# Schematic.net
KiCad netlist of a schematic drawn in Altium Designer
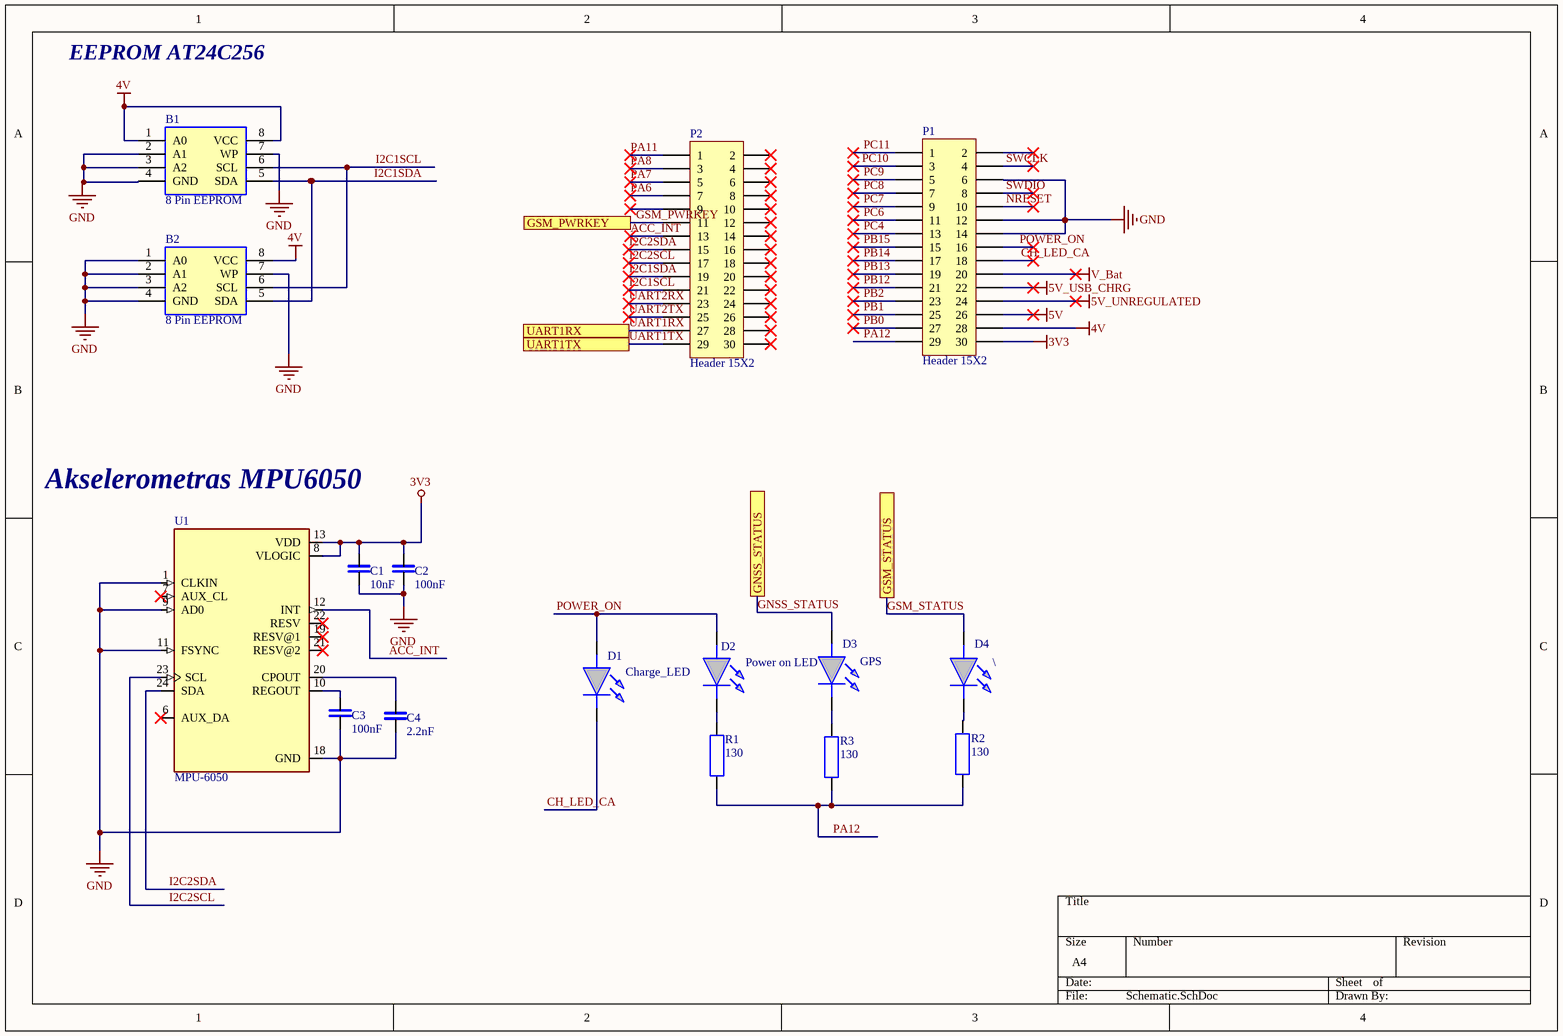
[diagram p0: Schematic.SchDoc]

(export (version "E")
  (design (tool "Eeschema 10.0.6"))
  (components
    (comp (ref "B1")
      (value "8 Pin EEPROM")
      (footprint "AT24C256")
      (fields
        (field (name "MANUFACTURER_PART_NUMBER") "AT24C256C-SSHL-T")
        (field (name "MOUSER PART NUMBER") "556-AT24C256C-SSHL-T")
      )
      (libsource (lib "IC") (part "AT24C256C"))
    )
    (comp (ref "B2")
      (value "8 Pin EEPROM")
      (footprint "AT24C256")
      (fields
        (field (name "MANUFACTURER_PART_NUMBER") "AT24C256C-SSHL-T")
        (field (name "MOUSER PART NUMBER") "556-AT24C256C-SSHL-T")
      )
      (libsource (lib "IC") (part "AT24C256C"))
    )
    (comp (ref "C1")
      (value "10nF")
      (footprint "CAP_0805")
      (fields (field (name "MP") "LD051A270KAB2A"))
      (libsource (lib "Passive_Components") (part "SMT_CAP"))
    )
    (comp (ref "C2")
      (value "100nF")
      (footprint "CAP_0805")
      (fields (field (name "MP") "LD051A270KAB2A"))
      (libsource (lib "Passive_Components") (part "SMT_CAP"))
    )
    (comp (ref "C3")
      (value "100nF")
      (footprint "CAP_0805")
      (fields (field (name "MP") "LD051A270KAB2A"))
      (libsource (lib "Passive_Components") (part "SMT_CAP"))
    )
    (comp (ref "C4")
      (value "2.2nF")
      (footprint "CAP_0805")
      (fields (field (name "MP") "LD051A270KAB2A"))
      (libsource (lib "Passive_Components") (part "SMT_CAP"))
    )
    (comp (ref "D1")
      (value "Charge_LED")
      (footprint "LED_0805")
      (fields
        (field (name "MANUFACTURER_PART_NUMBER") "HSMH-C170")
        (field (name "MOUSER PART NUMBER") "630-HSMH-C170")
      )
      (libsource (lib "Diodes") (part "LED"))
    )
    (comp (ref "D2")
      (value "Power on LED")
      (footprint "LED_0805")
      (fields
        (field (name "MANUFACTURER_PART_NUMBER") "HSMH-C170")
        (field (name "MOUSER PART NUMBER") "630-HSMH-C170")
      )
      (libsource (lib "Diodes") (part "LED"))
    )
    (comp (ref "D3")
      (value "GPS")
      (footprint "LED_0805")
      (fields
        (field (name "MANUFACTURER_PART_NUMBER") "HSMH-C170")
        (field (name "MOUSER PART NUMBER") "630-HSMH-C170")
      )
      (libsource (lib "Diodes") (part "LED"))
    )
    (comp (ref "D4")
      (value "\\")
      (footprint "LED_0805")
      (fields
        (field (name "MANUFACTURER_PART_NUMBER") "HSMH-C170")
        (field (name "MOUSER PART NUMBER") "630-HSMH-C170")
      )
      (libsource (lib "Diodes") (part "LED"))
    )
    (comp (ref "P1")
      (value "Header 15X2")
      (footprint "HDR2X15")
      (description "Header, 15-Pin, Dual row")
      (fields (field (name "PUBLISHER") "Altium Limited"))
      (libsource (lib "Miscellaneous Connectors") (part "Header 15X2"))
    )
    (comp (ref "P2")
      (value "Header 15X2")
      (footprint "HDR2X15")
      (description "Header, 15-Pin, Dual row")
      (fields (field (name "PUBLISHER") "Altium Limited"))
      (libsource (lib "Miscellaneous Connectors") (part "Header 15X2"))
    )
    (comp (ref "R1")
      (value "130")
      (footprint "RES_0805")
      (fields
        (field (name "MP") "2-2176053-0")
        (field (name "TOLERANCE") "1%")
        (field (name "MF") "TE Connectivity")
      )
      (libsource (lib "Passive_Components") (part "SMT_RES"))
    )
    (comp (ref "R2")
      (value "130")
      (footprint "RES_0805")
      (fields
        (field (name "MP") "2-2176053-0")
        (field (name "TOLERANCE") "1%")
        (field (name "MF") "TE Connectivity")
      )
      (libsource (lib "Passive_Components") (part "SMT_RES"))
    )
    (comp (ref "R3")
      (value "130")
      (footprint "RES_0805")
      (fields
        (field (name "MP") "2-2176053-0")
        (field (name "TOLERANCE") "1%")
        (field (name "MF") "TE Connectivity")
      )
      (libsource (lib "Passive_Components") (part "SMT_RES"))
    )
    (comp (ref "U1")
      (value "MPU-6050")
      (footprint "MPU_6050")
      (fields (field (name "MF") "TDK InvenSense"))
      (libsource (lib "IC") (part "MPU-6050"))
    )
  )
  (nets
    (net (code "2") (name "/ACC_INT") (class "Default")
      (node (ref "P2") (pin "13") (pinfunction "13_13") (pintype "passive"))
      (node (ref "U1") (pin "12") (pinfunction "INT_12") (pintype "output"))
    )
    (net (code "3") (name "/CH_LED_CA") (class "Default")
      (node (ref "D1") (pin "1") (pinfunction "K_1") (pintype "passive"))
      (node (ref "P1") (pin "18") (pinfunction "18_18") (pintype "passive"))
    )
    (net (code "4") (name "/GNSS_STATUS") (class "Default")
      (node (ref "D3") (pin "2") (pinfunction "A_2") (pintype "passive"))
    )
    (net (code "5") (name "/GSM_PWRKEY") (class "Default")
      (node (ref "P2") (pin "11") (pinfunction "11_11") (pintype "passive"))
    )
    (net (code "6") (name "/GSM_STATUS") (class "Default")
      (node (ref "D4") (pin "2") (pinfunction "A_2") (pintype "passive"))
    )
    (net (code "7") (name "/I2C1SCL") (class "Default")
      (node (ref "B1") (pin "6") (pinfunction "SCL_6") (pintype "passive"))
      (node (ref "B2") (pin "6") (pinfunction "SCL_6") (pintype "passive"))
      (node (ref "P2") (pin "21") (pinfunction "21_21") (pintype "passive"))
    )
    (net (code "8") (name "/I2C1SDA") (class "Default")
      (node (ref "B1") (pin "5") (pinfunction "SDA_5") (pintype "passive"))
      (node (ref "B2") (pin "5") (pinfunction "SDA_5") (pintype "passive"))
      (node (ref "P2") (pin "19") (pinfunction "19_19") (pintype "passive"))
    )
    (net (code "9") (name "/I2C2SCL") (class "Default")
      (node (ref "P2") (pin "17") (pinfunction "17_17") (pintype "passive"))
      (node (ref "U1") (pin "23") (pinfunction "SCL_23") (pintype "input"))
    )
    (net (code "10") (name "/I2C2SDA") (class "Default")
      (node (ref "P2") (pin "15") (pinfunction "15_15") (pintype "passive"))
      (node (ref "U1") (pin "24") (pinfunction "SDA_24") (pintype "bidirectional"))
    )
    (net (code "11") (name "/NRESET") (class "Default")
      (node (ref "P1") (pin "10") (pinfunction "10_10") (pintype "passive+no_connect"))
    )
    (net (code "12") (name "/PA6") (class "Default")
      (node (ref "P2") (pin "7") (pinfunction "7_7") (pintype "passive+no_connect"))
    )
    (net (code "13") (name "/PA7") (class "Default")
      (node (ref "P2") (pin "5") (pinfunction "5_5") (pintype "passive+no_connect"))
    )
    (net (code "14") (name "/PA8") (class "Default")
      (node (ref "P2") (pin "3") (pinfunction "3_3") (pintype "passive+no_connect"))
    )
    (net (code "15") (name "/PA11") (class "Default")
      (node (ref "P2") (pin "1") (pinfunction "1_1") (pintype "passive+no_connect"))
    )
    (net (code "16") (name "/PA12") (class "Default")
      (node (ref "P1") (pin "29") (pinfunction "29_29") (pintype "passive"))
      (node (ref "R1") (pin "1") (pinfunction "1_1") (pintype "passive"))
      (node (ref "R2") (pin "1") (pinfunction "1_1") (pintype "passive"))
      (node (ref "R3") (pin "1") (pinfunction "1_1") (pintype "passive"))
    )
    (net (code "17") (name "/PB0") (class "Default")
      (node (ref "P1") (pin "27") (pinfunction "27_27") (pintype "passive+no_connect"))
    )
    (net (code "18") (name "/PB1") (class "Default")
      (node (ref "P1") (pin "25") (pinfunction "25_25") (pintype "passive+no_connect"))
    )
    (net (code "19") (name "/PB2") (class "Default")
      (node (ref "P1") (pin "23") (pinfunction "23_23") (pintype "passive+no_connect"))
    )
    (net (code "20") (name "/PB12") (class "Default")
      (node (ref "P1") (pin "21") (pinfunction "21_21") (pintype "passive+no_connect"))
    )
    (net (code "21") (name "/PB13") (class "Default")
      (node (ref "P1") (pin "19") (pinfunction "19_19") (pintype "passive+no_connect"))
    )
    (net (code "22") (name "/PB14") (class "Default")
      (node (ref "P1") (pin "17") (pinfunction "17_17") (pintype "passive+no_connect"))
    )
    (net (code "23") (name "/PB15") (class "Default")
      (node (ref "P1") (pin "15") (pinfunction "15_15") (pintype "passive+no_connect"))
    )
    (net (code "24") (name "/PC4") (class "Default")
      (node (ref "P1") (pin "13") (pinfunction "13_13") (pintype "passive+no_connect"))
    )
    (net (code "25") (name "/PC6") (class "Default")
      (node (ref "P1") (pin "11") (pinfunction "11_11") (pintype "passive+no_connect"))
    )
    (net (code "26") (name "/PC7") (class "Default")
      (node (ref "P1") (pin "9") (pinfunction "9_9") (pintype "passive+no_connect"))
    )
    (net (code "27") (name "/PC8") (class "Default")
      (node (ref "P1") (pin "7") (pinfunction "7_7") (pintype "passive+no_connect"))
    )
    (net (code "28") (name "/PC9") (class "Default")
      (node (ref "P1") (pin "5") (pinfunction "5_5") (pintype "passive+no_connect"))
    )
    (net (code "29") (name "/PC10") (class "Default")
      (node (ref "P1") (pin "3") (pinfunction "3_3") (pintype "passive+no_connect"))
    )
    (net (code "30") (name "/PC11") (class "Default")
      (node (ref "P1") (pin "1") (pinfunction "1_1") (pintype "passive+no_connect"))
    )
    (net (code "31") (name "/POWER_ON") (class "Default")
      (node (ref "D1") (pin "2") (pinfunction "A_2") (pintype "passive"))
      (node (ref "D2") (pin "2") (pinfunction "A_2") (pintype "passive"))
      (node (ref "P1") (pin "16") (pinfunction "16_16") (pintype "passive"))
    )
    (net (code "32") (name "/SWCLK") (class "Default")
      (node (ref "P1") (pin "4") (pinfunction "4_4") (pintype "passive+no_connect"))
    )
    (net (code "33") (name "/SWDIO") (class "Default")
      (node (ref "P1") (pin "8") (pinfunction "8_8") (pintype "passive+no_connect"))
    )
    (net (code "34") (name "/UART1RX") (class "Default")
      (node (ref "P2") (pin "27") (pinfunction "27_27") (pintype "passive"))
    )
    (net (code "35") (name "/UART1TX") (class "Default")
      (node (ref "P2") (pin "29") (pinfunction "29_29") (pintype "passive"))
    )
    (net (code "36") (name "/UART2RX") (class "Default")
      (node (ref "P2") (pin "23") (pinfunction "23_23") (pintype "passive+no_connect"))
    )
    (net (code "37") (name "/UART2TX") (class "Default")
      (node (ref "P2") (pin "25") (pinfunction "25_25") (pintype "passive+no_connect"))
    )
    (net (code "38") (name "3V3") (class "Default")
      (node (ref "C1") (pin "2") (pinfunction "2_2") (pintype "passive"))
      (node (ref "C2") (pin "2") (pinfunction "2_2") (pintype "passive"))
      (node (ref "P1") (pin "30") (pinfunction "30_30") (pintype "passive"))
      (node (ref "U1") (pin "13") (pinfunction "VDD_13") (pintype "power_in"))
      (node (ref "U1") (pin "8") (pinfunction "VLOGIC_8") (pintype "power_in"))
    )
    (net (code "39") (name "4V") (class "Default")
      (node (ref "B1") (pin "1") (pinfunction "A0_1") (pintype "passive"))
      (node (ref "B1") (pin "8") (pinfunction "VCC_8") (pintype "passive"))
      (node (ref "B2") (pin "8") (pinfunction "VCC_8") (pintype "passive"))
      (node (ref "P1") (pin "28") (pinfunction "28_28") (pintype "passive"))
    )
    (net (code "40") (name "5V") (class "Default")
      (node (ref "P1") (pin "26") (pinfunction "26_26") (pintype "passive"))
    )
    (net (code "41") (name "5V_UNREGULATED") (class "Default")
      (node (ref "P1") (pin "24") (pinfunction "24_24") (pintype "passive"))
    )
    (net (code "42") (name "5V_USB_CHRG") (class "Default")
      (node (ref "P1") (pin "22") (pinfunction "22_22") (pintype "passive"))
    )
    (net (code "43") (name "GND") (class "Default")
      (node (ref "B1") (pin "2") (pinfunction "A1_2") (pintype "passive"))
      (node (ref "B1") (pin "3") (pinfunction "A2_3") (pintype "passive"))
      (node (ref "B1") (pin "4") (pinfunction "GND_4") (pintype "passive"))
      (node (ref "B1") (pin "7") (pinfunction "WP_7") (pintype "passive"))
      (node (ref "B2") (pin "1") (pinfunction "A0_1") (pintype "passive"))
      (node (ref "B2") (pin "2") (pinfunction "A1_2") (pintype "passive"))
      (node (ref "B2") (pin "3") (pinfunction "A2_3") (pintype "passive"))
      (node (ref "B2") (pin "4") (pinfunction "GND_4") (pintype "passive"))
      (node (ref "B2") (pin "7") (pinfunction "WP_7") (pintype "passive"))
      (node (ref "C1") (pin "1") (pinfunction "1_1") (pintype "passive"))
      (node (ref "C2") (pin "1") (pinfunction "1_1") (pintype "passive"))
      (node (ref "C3") (pin "1") (pinfunction "1_1") (pintype "passive"))
      (node (ref "C4") (pin "1") (pinfunction "1_1") (pintype "passive"))
      (node (ref "P1") (pin "12") (pinfunction "12_12") (pintype "passive"))
      (node (ref "P1") (pin "14") (pinfunction "14_14") (pintype "passive"))
      (node (ref "P1") (pin "6") (pinfunction "6_6") (pintype "passive"))
      (node (ref "U1") (pin "1") (pinfunction "CLKIN_1") (pintype "input"))
      (node (ref "U1") (pin "11") (pinfunction "FSYNC_11") (pintype "input"))
      (node (ref "U1") (pin "18") (pinfunction "GND_18") (pintype "power_in"))
      (node (ref "U1") (pin "9") (pinfunction "AD0_9") (pintype "input"))
    )
    (net (code "44") (name "Net-(D2-K)") (class "Default")
      (node (ref "D2") (pin "1") (pinfunction "K_1") (pintype "passive"))
      (node (ref "R1") (pin "2") (pinfunction "2_2") (pintype "passive"))
    )
    (net (code "45") (name "Net-(D3-K)") (class "Default")
      (node (ref "D3") (pin "1") (pinfunction "K_1") (pintype "passive"))
      (node (ref "R3") (pin "2") (pinfunction "2_2") (pintype "passive"))
    )
    (net (code "46") (name "Net-(D4-K)") (class "Default")
      (node (ref "D4") (pin "1") (pinfunction "K_1") (pintype "passive"))
      (node (ref "R2") (pin "2") (pinfunction "2_2") (pintype "passive"))
    )
    (net (code "47") (name "Net-(U1-CPOUT)") (class "Default")
      (node (ref "C4") (pin "2") (pinfunction "2_2") (pintype "passive"))
      (node (ref "U1") (pin "20") (pinfunction "CPOUT_20") (pintype "passive"))
    )
    (net (code "48") (name "Net-(U1-REGOUT)") (class "Default")
      (node (ref "C3") (pin "2") (pinfunction "2_2") (pintype "passive"))
      (node (ref "U1") (pin "10") (pinfunction "REGOUT_10") (pintype "passive"))
    )
    (net (code "49") (name "V_Bat") (class "Default")
      (node (ref "P1") (pin "20") (pinfunction "20_20") (pintype "passive"))
    )
    (net (code "50") (name "unconnected-(P1-Pad2)") (class "Default")
      (node (ref "P1") (pin "2") (pinfunction "2_2") (pintype "passive+no_connect"))
    )
    (net (code "51") (name "unconnected-(P2-Pad2)") (class "Default")
      (node (ref "P2") (pin "2") (pinfunction "2_2") (pintype "passive+no_connect"))
    )
    (net (code "52") (name "unconnected-(P2-Pad4)") (class "Default")
      (node (ref "P2") (pin "4") (pinfunction "4_4") (pintype "passive+no_connect"))
    )
    (net (code "53") (name "unconnected-(P2-Pad6)") (class "Default")
      (node (ref "P2") (pin "6") (pinfunction "6_6") (pintype "passive+no_connect"))
    )
    (net (code "54") (name "unconnected-(P2-Pad8)") (class "Default")
      (node (ref "P2") (pin "8") (pinfunction "8_8") (pintype "passive+no_connect"))
    )
    (net (code "55") (name "unconnected-(P2-Pad9)") (class "Default")
      (node (ref "P2") (pin "9") (pinfunction "9_9") (pintype "passive+no_connect"))
    )
    (net (code "56") (name "unconnected-(P2-Pad10)") (class "Default")
      (node (ref "P2") (pin "10") (pinfunction "10_10") (pintype "passive+no_connect"))
    )
    (net (code "57") (name "unconnected-(P2-Pad12)") (class "Default")
      (node (ref "P2") (pin "12") (pinfunction "12_12") (pintype "passive+no_connect"))
    )
    (net (code "58") (name "unconnected-(P2-Pad14)") (class "Default")
      (node (ref "P2") (pin "14") (pinfunction "14_14") (pintype "passive+no_connect"))
    )
    (net (code "59") (name "unconnected-(P2-Pad16)") (class "Default")
      (node (ref "P2") (pin "16") (pinfunction "16_16") (pintype "passive+no_connect"))
    )
    (net (code "60") (name "unconnected-(P2-Pad18)") (class "Default")
      (node (ref "P2") (pin "18") (pinfunction "18_18") (pintype "passive+no_connect"))
    )
    (net (code "61") (name "unconnected-(P2-Pad20)") (class "Default")
      (node (ref "P2") (pin "20") (pinfunction "20_20") (pintype "passive+no_connect"))
    )
    (net (code "62") (name "unconnected-(P2-Pad22)") (class "Default")
      (node (ref "P2") (pin "22") (pinfunction "22_22") (pintype "passive+no_connect"))
    )
    (net (code "63") (name "unconnected-(P2-Pad24)") (class "Default")
      (node (ref "P2") (pin "24") (pinfunction "24_24") (pintype "passive+no_connect"))
    )
    (net (code "64") (name "unconnected-(P2-Pad26)") (class "Default")
      (node (ref "P2") (pin "26") (pinfunction "26_26") (pintype "passive+no_connect"))
    )
    (net (code "65") (name "unconnected-(P2-Pad28)") (class "Default")
      (node (ref "P2") (pin "28") (pinfunction "28_28") (pintype "passive+no_connect"))
    )
    (net (code "66") (name "unconnected-(P2-Pad30)") (class "Default")
      (node (ref "P2") (pin "30") (pinfunction "30_30") (pintype "passive+no_connect"))
    )
    (net (code "67") (name "unconnected-(U1-AUX_CL-Pad7)") (class "Default")
      (node (ref "U1") (pin "7") (pinfunction "AUX_CL_7") (pintype "input+no_connect"))
    )
    (net (code "68") (name "unconnected-(U1-AUX_DA-Pad6)") (class "Default")
      (node (ref "U1") (pin "6") (pinfunction "AUX_DA_6") (pintype "bidirectional+no_connect"))
    )
    (net (code "69") (name "unconnected-(U1-RESV-Pad22)") (class "Default")
      (node (ref "U1") (pin "22") (pinfunction "RESV_22") (pintype "passive+no_connect"))
    )
    (net (code "70") (name "unconnected-(U1-RESV@1-Pad19)") (class "Default")
      (node (ref "U1") (pin "19") (pinfunction "RESV@1_19") (pintype "passive+no_connect"))
    )
    (net (code "71") (name "unconnected-(U1-RESV@2-Pad21)") (class "Default")
      (node (ref "U1") (pin "21") (pinfunction "RESV@2_21") (pintype "passive+no_connect"))
    )
  )
)
